# ext_power_M.net
KiCad netlist of a schematic drawn in EAGLE
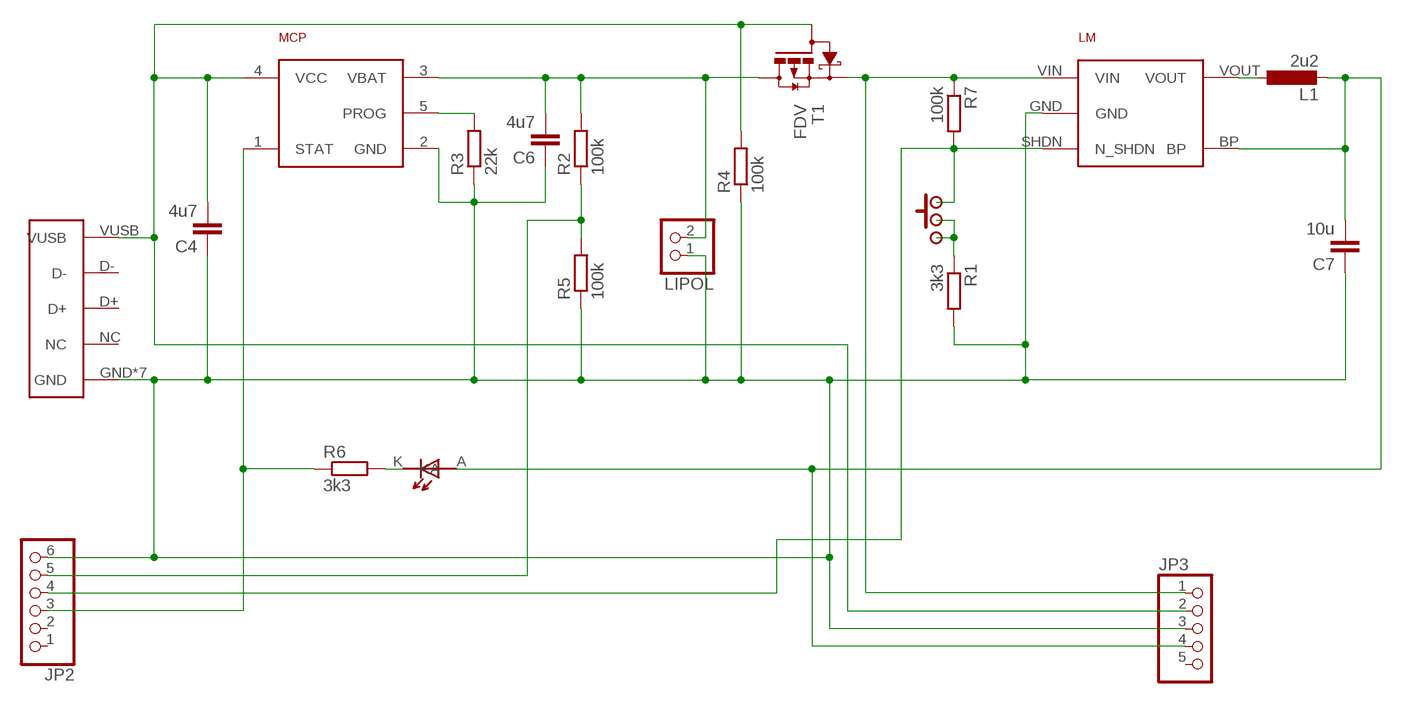
[diagram p0: schematic, sheet 1]

(export (version "E")
  (design (tool "Eeschema 10.0.6"))
  (components
    (comp (ref "C4")
      (value "4u7")
      (footprint "eagle-import:C0603")
      (libsource (lib "eagle-import") (part "C-EUC0603"))
    )
    (comp (ref "C6")
      (value "4u7")
      (footprint "eagle-import:C0603")
      (libsource (lib "eagle-import") (part "C-EUC0603"))
    )
    (comp (ref "C7")
      (value "10u")
      (footprint "eagle-import:C0603")
      (libsource (lib "eagle-import") (part "C-EUC0603"))
    )
    (comp (ref "D1")
      (value "LED1.8")
      (footprint "eagle-import:LED1.8")
      (libsource (lib "eagle-import") (part "LED1.8"))
    )
    (comp (ref "JP2")
      (value "PINHD-1X6")
      (footprint "eagle-import:1X06")
      (libsource (lib "eagle-import") (part "PINHD-1X6"))
    )
    (comp (ref "JP3")
      (value "PINHD-1X5")
      (footprint "eagle-import:1X05")
      (libsource (lib "eagle-import") (part "PINHD-1X5"))
    )
    (comp (ref "L1")
      (value "2u2")
      (footprint "eagle-import:L3230M")
      (libsource (lib "eagle-import") (part "L-EUL3230M"))
    )
    (comp (ref "LIPOL")
      (value "PINHD-1X2")
      (footprint "eagle-import:1X02")
      (libsource (lib "eagle-import") (part "PINHD-1X2"))
    )
    (comp (ref "LM")
      (value "TC")
      (footprint "eagle-import:SOT32-5")
      (libsource (lib "eagle-import") (part "STABILISER_APE8865"))
    )
    (comp (ref "MCP")
      (value "MCP")
      (footprint "eagle-import:SOT23-5")
      (libsource (lib "eagle-import") (part "MCP73831"))
    )
    (comp (ref "ON/OFF/RESET")
      (value "SWITCH")
      (footprint "eagle-import:SWITCH")
      (libsource (lib "eagle-import") (part "SWITCH"))
    )
    (comp (ref "R1")
      (value "3k3")
      (footprint "eagle-import:R0603")
      (libsource (lib "eagle-import") (part "R-EU_R0603"))
    )
    (comp (ref "R2")
      (value "100k")
      (footprint "eagle-import:R0603")
      (libsource (lib "eagle-import") (part "R-EU_R0603"))
    )
    (comp (ref "R3")
      (value "22k")
      (footprint "eagle-import:R0603")
      (libsource (lib "eagle-import") (part "R-EU_R0603"))
    )
    (comp (ref "R4")
      (value "100k")
      (footprint "eagle-import:R0603")
      (libsource (lib "eagle-import") (part "R-EU_R0603"))
    )
    (comp (ref "R5")
      (value "100k")
      (footprint "eagle-import:R0603")
      (libsource (lib "eagle-import") (part "R-EU_R0603"))
    )
    (comp (ref "R6")
      (value "3k3")
      (footprint "eagle-import:R0603")
      (libsource (lib "eagle-import") (part "R-EU_R0603"))
    )
    (comp (ref "R7")
      (value "100k")
      (footprint "eagle-import:R0603")
      (libsource (lib "eagle-import") (part "R-EU_R0603"))
    )
    (comp (ref "T1")
      (value "FDV")
      (footprint "eagle-import:SOT23")
      (libsource (lib "eagle-import") (part "P-MOSFET-FDV304P"))
    )
    (comp (ref "USB")
      (value "MICRO-USB")
      (footprint "eagle-import:MICRO-USB")
      (libsource (lib "eagle-import") (part "MICRO-USB"))
    )
  )
  (nets
    (net (code "1") (name "Net-(C7-Pad2)") (class "Default")
      (node (ref "C7") (pin "2") (pinfunction "2_2") (pintype "passive"))
      (node (ref "D1") (pin "A") (pinfunction "A_A") (pintype "bidirectional"))
      (node (ref "JP3") (pin "4") (pinfunction "4_4") (pintype "passive"))
      (node (ref "L1") (pin "2") (pinfunction "2_2") (pintype "passive"))
      (node (ref "LM") (pin "BP") (pinfunction "BP_BP") (pintype "bidirectional"))
    )
    (net (code "2") (name "Net-(D1-PadK)") (class "Default")
      (node (ref "D1") (pin "K") (pinfunction "K_K") (pintype "bidirectional"))
      (node (ref "R6") (pin "2") (pinfunction "2_2") (pintype "passive"))
    )
    (net (code "3") (name "Net-(JP2-Pad5)") (class "Default")
      (node (ref "JP2") (pin "5") (pinfunction "5_5") (pintype "passive"))
      (node (ref "R2") (pin "1") (pinfunction "1_1") (pintype "passive"))
      (node (ref "R5") (pin "2") (pinfunction "2_2") (pintype "passive"))
    )
    (net (code "4") (name "Net-(JP3-Pad1)") (class "Default")
      (node (ref "JP3") (pin "1") (pinfunction "1_1") (pintype "passive"))
      (node (ref "LM") (pin "VIN") (pinfunction "VIN_VIN") (pintype "bidirectional"))
      (node (ref "R7") (pin "1") (pinfunction "1_1") (pintype "passive"))
      (node (ref "T1") (pin "S") (pinfunction "S_S") (pintype "passive"))
    )
    (net (code "5") (name "Net-(L1-Pad1)") (class "Default")
      (node (ref "L1") (pin "1") (pinfunction "1_1") (pintype "passive"))
      (node (ref "LM") (pin "VOUT") (pinfunction "VOUT_VOUT") (pintype "bidirectional"))
    )
    (net (code "6") (name "Net-(LM-N_SHDN)") (class "Default")
      (node (ref "JP2") (pin "4") (pinfunction "4_4") (pintype "passive"))
      (node (ref "LM") (pin "SHDN") (pinfunction "N_SHDN_SHDN") (pintype "bidirectional"))
      (node (ref "ON/OFF/RESET") (pin "P$1") (pinfunction "P$1_P$1") (pintype "bidirectional"))
      (node (ref "ON/OFF/RESET") (pin "P$4") (pinfunction "P$1_P$4") (pintype "bidirectional"))
      (node (ref "R7") (pin "2") (pinfunction "2_2") (pintype "passive"))
    )
    (net (code "7") (name "Net-(MCP-GND)") (class "Default")
      (node (ref "C4") (pin "1") (pinfunction "1_1") (pintype "passive"))
      (node (ref "C6") (pin "1") (pinfunction "1_1") (pintype "passive"))
      (node (ref "C7") (pin "1") (pinfunction "1_1") (pintype "passive"))
      (node (ref "JP2") (pin "6") (pinfunction "6_6") (pintype "passive"))
      (node (ref "JP3") (pin "3") (pinfunction "3_3") (pintype "passive"))
      (node (ref "LIPOL") (pin "1") (pinfunction "1_1") (pintype "passive"))
      (node (ref "LM") (pin "GND") (pinfunction "GND_GND") (pintype "bidirectional"))
      (node (ref "MCP") (pin "2") (pinfunction "GND_2") (pintype "bidirectional"))
      (node (ref "R1") (pin "2") (pinfunction "2_2") (pintype "passive"))
      (node (ref "R3") (pin "1") (pinfunction "1_1") (pintype "passive"))
      (node (ref "R4") (pin "1") (pinfunction "1_1") (pintype "passive"))
      (node (ref "R5") (pin "1") (pinfunction "1_1") (pintype "passive"))
      (node (ref "USB") (pin "GND") (pinfunction "GND_GND") (pintype "bidirectional"))
      (node (ref "USB") (pin "GND1") (pinfunction "GND_GND1") (pintype "bidirectional"))
      (node (ref "USB") (pin "GND2") (pinfunction "GND_GND2") (pintype "bidirectional"))
      (node (ref "USB") (pin "GND3") (pinfunction "GND_GND3") (pintype "bidirectional"))
      (node (ref "USB") (pin "GND4") (pinfunction "GND_GND4") (pintype "bidirectional"))
      (node (ref "USB") (pin "P$1") (pinfunction "GND_P$1") (pintype "bidirectional"))
      (node (ref "USB") (pin "P$2") (pinfunction "GND_P$2") (pintype "bidirectional"))
    )
    (net (code "8") (name "Net-(MCP-PROG)") (class "Default")
      (node (ref "MCP") (pin "5") (pinfunction "PROG_5") (pintype "bidirectional"))
      (node (ref "R3") (pin "2") (pinfunction "2_2") (pintype "passive"))
    )
    (net (code "9") (name "Net-(MCP-STAT)") (class "Default")
      (node (ref "JP2") (pin "3") (pinfunction "3_3") (pintype "passive"))
      (node (ref "MCP") (pin "1") (pinfunction "STAT_1") (pintype "bidirectional"))
      (node (ref "R6") (pin "1") (pinfunction "1_1") (pintype "passive"))
    )
    (net (code "10") (name "Net-(MCP-VBAT)") (class "Default")
      (node (ref "C6") (pin "2") (pinfunction "2_2") (pintype "passive"))
      (node (ref "LIPOL") (pin "2") (pinfunction "2_2") (pintype "passive"))
      (node (ref "MCP") (pin "3") (pinfunction "VBAT_3") (pintype "bidirectional"))
      (node (ref "R2") (pin "2") (pinfunction "2_2") (pintype "passive"))
      (node (ref "T1") (pin "D") (pinfunction "D_D") (pintype "passive"))
    )
    (net (code "11") (name "Net-(MCP-VCC)") (class "Default")
      (node (ref "C4") (pin "2") (pinfunction "2_2") (pintype "passive"))
      (node (ref "JP3") (pin "2") (pinfunction "2_2") (pintype "passive"))
      (node (ref "MCP") (pin "4") (pinfunction "VCC_4") (pintype "bidirectional"))
      (node (ref "R4") (pin "2") (pinfunction "2_2") (pintype "passive"))
      (node (ref "T1") (pin "G") (pinfunction "G_G") (pintype "passive"))
      (node (ref "USB") (pin "VUSB") (pinfunction "VUSB_VUSB") (pintype "bidirectional"))
    )
    (net (code "12") (name "Net-(ON/OFF/RESET-P$3-PadP$5)") (class "Default")
      (node (ref "ON/OFF/RESET") (pin "P$2") (pinfunction "P$2_P$2") (pintype "bidirectional"))
      (node (ref "ON/OFF/RESET") (pin "P$3") (pinfunction "P$3_P$3") (pintype "bidirectional"))
      (node (ref "ON/OFF/RESET") (pin "P$5") (pinfunction "P$3_P$5") (pintype "bidirectional"))
      (node (ref "R1") (pin "1") (pinfunction "1_1") (pintype "passive"))
    )
    (net (code "13") (name "unconnected-(JP2-Pad1)") (class "Default")
      (node (ref "JP2") (pin "1") (pinfunction "1_1") (pintype "passive"))
    )
    (net (code "14") (name "unconnected-(JP2-Pad2)") (class "Default")
      (node (ref "JP2") (pin "2") (pinfunction "2_2") (pintype "passive"))
    )
    (net (code "15") (name "unconnected-(JP3-Pad5)") (class "Default")
      (node (ref "JP3") (pin "5") (pinfunction "5_5") (pintype "passive"))
    )
    (net (code "16") (name "unconnected-(USB-PadD+)") (class "Default")
      (node (ref "USB") (pin "D+") (pinfunction "D+_D+") (pintype "bidirectional"))
    )
    (net (code "17") (name "unconnected-(USB-PadD-)") (class "Default")
      (node (ref "USB") (pin "D-") (pinfunction "D-_D-") (pintype "bidirectional"))
    )
    (net (code "18") (name "unconnected-(USB-PadNC)") (class "Default")
      (node (ref "USB") (pin "NC") (pinfunction "NC_NC") (pintype "bidirectional"))
    )
  )
)
